# 1_P1_schdoc.net
KiCad netlist of a schematic drawn in Altium Designer
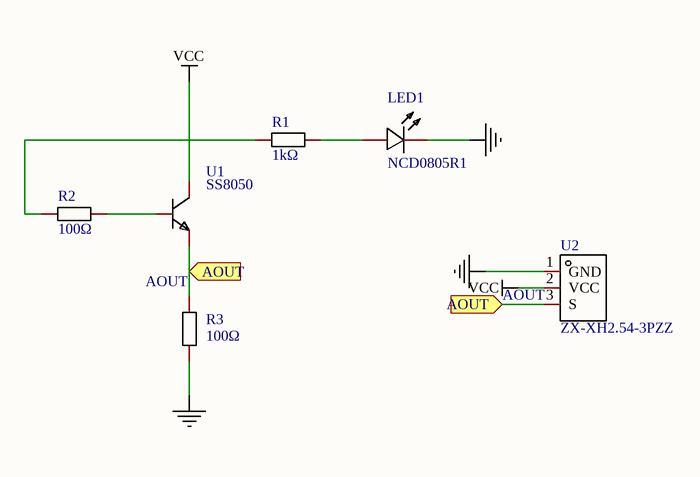
[diagram p0: 1_P1.schdoc.schdoc]

(export (version "E")
  (design (tool "Eeschema 10.0.6"))
  (components
    (comp (ref "LED1")
      (value "NCD0805R1")
      (fields (field (name "NAME") "NCD0805R1") (field (name "MANUFACTURER") "国星光电"))
      (libsource (lib "altium-import") (part "root_0_mirrored_NCD0805R1_"))
    )
    (comp (ref "R1")
      (value "1kΩ")
      (fields
        (field (name "NAME") "1kΩ")
        (field (name "MANUFACTURER") "UNI-ROYAL(厚声)")
        (field (name "MANUFACTURER PART") "0805W8F1001T5E")
        (field (name "TOLERANCE") "±1%")
      )
      (libsource (lib "altium-import") (part "root_0_0805W8F1001T5E_"))
    )
    (comp (ref "R2")
      (value "100Ω")
      (fields
        (field (name "NAME") "100Ω")
        (field (name "MANUFACTURER") "UNI-ROYAL(厚声)")
        (field (name "MANUFACTURER PART") "0805W8F1000T5E")
        (field (name "TOLERANCE") "±1%")
      )
      (libsource (lib "altium-import") (part "root_2_0805W8F1000T5E_"))
    )
    (comp (ref "R3")
      (value "100Ω")
      (fields
        (field (name "NAME") "100Ω")
        (field (name "MANUFACTURER") "UNI-ROYAL(厚声)")
        (field (name "MANUFACTURER PART") "0805W8F1000T5E")
        (field (name "TOLERANCE") "±1%")
      )
      (libsource (lib "altium-import") (part "root_1_0805W8F1000T5E_"))
    )
    (comp (ref "U1")
      (value "SS8050")
      (description "晶体管类型:NPN;集电极电流(Ic):1.5A;集射极击穿电压(Vceo):25V;功率(Pd):300mW;直流电流增益(hFE@Ic,Vce):120@100mA,1.0V;")
      (fields (field (name "NAME") "SS8050") (field (name "MANUFACTURER") "宏迦橙"))
      (libsource (lib "altium-import") (part "root_0_SS8050_C7420370_"))
    )
    (comp (ref "U2")
      (value "ZX-XH2.54-3PZZ")
      (fields (field (name "NAME") "ZX-XH2.54-3PZZ") (field (name "MANUFACTURER") "Megastar(兆星)"))
      (libsource (lib "altium-import") (part "root_0_水位传感器_"))
    )
  )
  (nets
    (net (code "1") (name "/AOUT") (class "Default")
      (node (ref "R3") (pin "2") (pinfunction "2_2") (pintype "passive"))
      (node (ref "U1") (pin "2") (pinfunction "E_2") (pintype "passive"))
      (node (ref "U2") (pin "3") (pinfunction "S_3") (pintype "passive"))
    )
    (net (code "2") (name "<NO NET>") (class "Default")
      (node (ref "LED1") (pin "2") (pinfunction "-_2") (pintype "passive"))
      (node (ref "R3") (pin "1") (pinfunction "1_1") (pintype "passive"))
      (node (ref "U2") (pin "1") (pinfunction "GND_1") (pintype "passive"))
    )
    (net (code "3") (name "Net-(LED1-+)") (class "Default")
      (node (ref "LED1") (pin "1") (pinfunction "+_1") (pintype "passive"))
      (node (ref "R1") (pin "2") (pinfunction "2_2") (pintype "passive"))
    )
    (net (code "4") (name "Net-(U1-B)") (class "Default")
      (node (ref "R2") (pin "1") (pinfunction "1_1") (pintype "passive"))
      (node (ref "U1") (pin "1") (pinfunction "B_1") (pintype "passive"))
    )
    (net (code "5") (name "VCC") (class "Default")
      (node (ref "R1") (pin "1") (pinfunction "1_1") (pintype "passive"))
      (node (ref "R2") (pin "2") (pinfunction "2_2") (pintype "passive"))
      (node (ref "U1") (pin "3") (pinfunction "C_3") (pintype "passive"))
      (node (ref "U2") (pin "2") (pinfunction "VCC_2") (pintype "passive"))
    )
  )
)
